# Power.net
KiCad netlist of a schematic drawn in Altium Designer
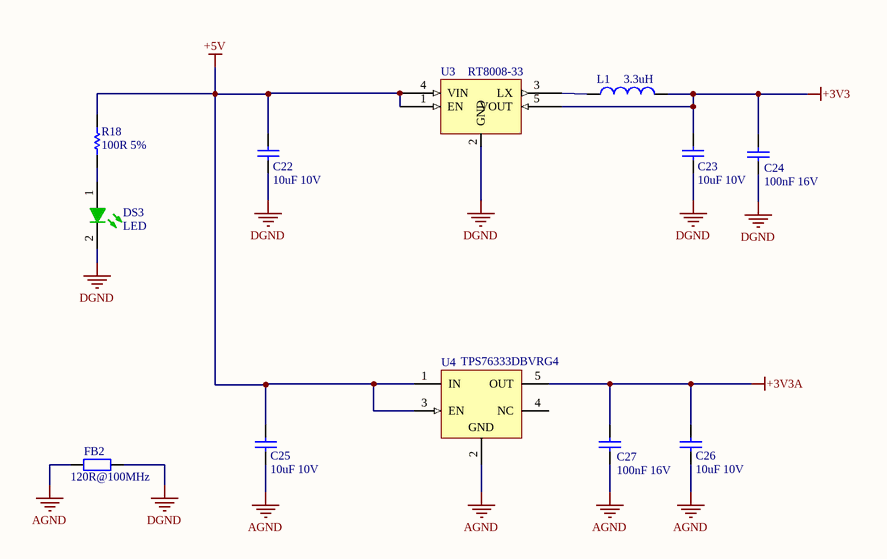
[diagram p0: Power.SchDoc]

(export (version "E")
  (design (tool "Eeschema 10.0.6"))
  (components
    (comp (ref "C22")
      (value "10uF 10V")
      (footprint "CAPC0603(1608)100_M")
      (description "CAP 10uF 10V ±10% 0603 (1608 Metric) Thickness 1mm SMD")
      (fields (field (name "TOLERANCE") "±10%"))
      (libsource (lib "Altium Content Vault") (part "CAP"))
    )
    (comp (ref "C23")
      (value "10uF 10V")
      (footprint "CAPC0603(1608)100_M")
      (description "CAP 10uF 10V ±10% 0603 (1608 Metric) Thickness 1mm SMD")
      (fields (field (name "TOLERANCE") "±10%"))
      (libsource (lib "Altium Content Vault") (part "CAP"))
    )
    (comp (ref "C24")
      (value "100nF 16V")
      (footprint "CAPC0603(1608)100_M")
      (description "CAP 100nF 16V ±10% 0603 (1608 Metric) Thickness 1mm SMD")
      (fields (field (name "TOLERANCE") "±10%"))
      (libsource (lib "Altium Content Vault") (part "CMP-1035-02584-1"))
    )
    (comp (ref "C25")
      (value "10uF 10V")
      (footprint "CAPC0603(1608)100_M")
      (description "CAP 10uF 10V ±10% 0603 (1608 Metric) Thickness 1mm SMD")
      (fields (field (name "TOLERANCE") "±10%"))
      (libsource (lib "Altium Content Vault") (part "CAP"))
    )
    (comp (ref "C26")
      (value "10uF 10V")
      (footprint "CAPC0603(1608)100_M")
      (description "CAP 10uF 10V ±10% 0603 (1608 Metric) Thickness 1mm SMD")
      (fields (field (name "TOLERANCE") "±10%"))
      (libsource (lib "Altium Content Vault") (part "CAP"))
    )
    (comp (ref "C27")
      (value "100nF 16V")
      (footprint "CAPC0603(1608)100_M")
      (description "CAP 100nF 16V ±10% 0603 (1608 Metric) Thickness 1mm SMD")
      (fields (field (name "TOLERANCE") "±10%"))
      (libsource (lib "Altium Content Vault") (part "CMP-1035-02584-1"))
    )
    (comp (ref "DS3")
      (value "LED")
      (footprint "KING-0603LED_GREEN_V")
      (description "LED, SMT, 0603(1608), 1.1mm thickness, Green")
      (fields (field (name "MANUFACTURER") "Kingbright") (field (name "PARTNUMBER") "KP-1608MGC"))
      (libsource (lib "Altium Content Vault") (part "CMP-0404-00001-1"))
    )
    (comp (ref "FB2")
      (value "120R@100MHz")
      (footprint "RESC1608N")
      (description "Resistor")
      (fields (field (name "PUBLISHER") "Altium Limited"))
      (libsource (lib "Miscellaneous Devices") (part "Res2"))
    )
    (comp (ref "L1")
      (value "3.3uH")
      (footprint "INDC2012N")
      (description "Inductor")
      (fields (field (name "PUBLISHER") "Altium Limited"))
      (libsource (lib "Miscellaneous Devices") (part "Inductor"))
    )
    (comp (ref "R18")
      (value "100R 5%")
      (footprint "RESC0603(1608)_M")
      (description "100R 0.1W 5% 0603 (1608 Metric)  SMD")
      (fields (field (name "TOLERANCE") "5 %") (field (name "POWER") "0.1 W"))
      (libsource (lib "Altium Content Vault") (part "CMP-1012-00050-1"))
    )
    (comp (ref "U3")
      (value "RT8008-33")
      (footprint "SOT23-5AN")
      (description "RT8008")
      (libsource (lib "MCU") (part "RT8008"))
    )
    (comp (ref "U4")
      (value "TPS76333DBVRG4")
      (footprint "TI-DBV5_N")
      (fields (field (name "MANUFACTURER") "Texas Instruments"))
      (libsource (lib "Altium Content Vault") (part "TI-TXX7XXXX-5"))
    )
  )
  (nets
    (net (code "1") (name "+3V3") (class "Default")
      (node (ref "C23") (pin "2") (pinfunction "2_2") (pintype "passive"))
      (node (ref "C24") (pin "2") (pinfunction "2_2") (pintype "passive"))
      (node (ref "L1") (pin "2") (pinfunction "2_2") (pintype "passive"))
      (node (ref "U3") (pin "5") (pinfunction "VOUT_5") (pintype "input"))
    )
    (net (code "2") (name "+3V3A") (class "Default")
      (node (ref "C26") (pin "2") (pinfunction "2_2") (pintype "passive"))
      (node (ref "C27") (pin "2") (pinfunction "2_2") (pintype "passive"))
      (node (ref "U4") (pin "5") (pinfunction "OUT_5") (pintype "power_in"))
    )
    (net (code "3") (name "+5V") (class "Default")
      (node (ref "C22") (pin "2") (pinfunction "2_2") (pintype "passive"))
      (node (ref "C25") (pin "2") (pinfunction "2_2") (pintype "passive"))
      (node (ref "R18") (pin "2") (pinfunction "2_2") (pintype "passive"))
      (node (ref "U3") (pin "1") (pinfunction "EN_1") (pintype "input"))
      (node (ref "U3") (pin "4") (pinfunction "VIN_4") (pintype "input"))
      (node (ref "U4") (pin "1") (pinfunction "IN_1") (pintype "power_in"))
      (node (ref "U4") (pin "3") (pinfunction "EN_3") (pintype "input"))
    )
    (net (code "4") (name "AGND") (class "Default")
      (node (ref "C25") (pin "1") (pinfunction "1_1") (pintype "passive"))
      (node (ref "C26") (pin "1") (pinfunction "1_1") (pintype "passive"))
      (node (ref "C27") (pin "1") (pinfunction "1_1") (pintype "passive"))
      (node (ref "FB2") (pin "1") (pinfunction "1_1") (pintype "passive"))
      (node (ref "U4") (pin "2") (pinfunction "GND_2") (pintype "power_in"))
    )
    (net (code "5") (name "DGND") (class "Default")
      (node (ref "C22") (pin "1") (pinfunction "1_1") (pintype "passive"))
      (node (ref "C23") (pin "1") (pinfunction "1_1") (pintype "passive"))
      (node (ref "C24") (pin "1") (pinfunction "1_1") (pintype "passive"))
      (node (ref "DS3") (pin "2") (pinfunction "K_2") (pintype "passive"))
      (node (ref "FB2") (pin "2") (pinfunction "2_2") (pintype "passive"))
      (node (ref "U3") (pin "2") (pinfunction "GND_2") (pintype "passive"))
    )
    (net (code "6") (name "Net-(DS3-A)") (class "Default")
      (node (ref "DS3") (pin "1") (pinfunction "A_1") (pintype "passive"))
      (node (ref "R18") (pin "1") (pinfunction "1_1") (pintype "passive"))
    )
    (net (code "7") (name "Net-(U3-LX)") (class "Default")
      (node (ref "L1") (pin "1") (pinfunction "1_1") (pintype "passive"))
      (node (ref "U3") (pin "3") (pinfunction "LX_3") (pintype "output"))
    )
    (net (code "8") (name "unconnected-(U4-NC-Pad4)") (class "Default")
      (node (ref "U4") (pin "4") (pinfunction "NC_4") (pintype "passive"))
    )
  )
)
